# schem.net
KiCad netlist of a schematic drawn in Altium Designer
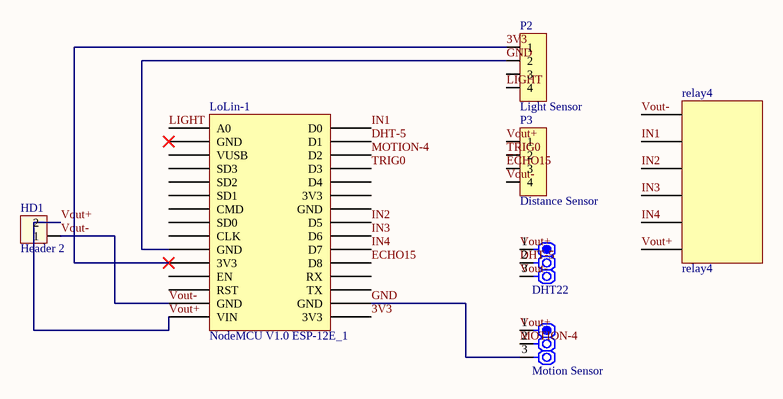
[diagram p0: schem.SchDoc]

(export (version "E")
  (design (tool "Eeschema 10.0.6"))
  (components
    (comp (ref "DHT22")
      (value "IO")
      (footprint "CON.HDR1X3")
      (description "Header 1x3")
      (fields (field (name "PUBLISHER") "Hoang Nguyen"))
      (libsource (lib "phong") (part "CON.HDR1x3"))
    )
    (comp (ref "HD1")
      (value "Header 2")
      (footprint "HED2")
      (description "Header 2 (Green)")
      (libsource (lib "syhaunguyen") (part "Hed2"))
    )
    (comp (ref "LoLin-1")
      (value "NodeMCU V1.0 ESP-12E_1")
      (footprint "LoLin NodeMcu V3")
      (description "LoLin NodeMCU V3")
      (libsource (lib "nodemcu") (part "NodeMCU V1.0 ESP-12E_1"))
    )
    (comp (ref "Motion Sensor")
      (value "IO")
      (footprint "CON.HDR1X3")
      (description "Header 1x3")
      (fields (field (name "PUBLISHER") "Hoang Nguyen"))
      (libsource (lib "phong") (part "CON.HDR1x3"))
    )
    (comp (ref "P2")
      (value "Light Sensor")
      (footprint "CON Header 4")
      (description "Header, 4-Pin")
      (libsource (lib "BKIT4U_LIB") (part "Header 4"))
    )
    (comp (ref "P3")
      (value "Distance Sensor")
      (footprint "CON Header 4")
      (description "Header, 4-Pin")
      (libsource (lib "BKIT4U_LIB") (part "Header 4"))
    )
    (comp (ref "relay4")
      (value "relay4")
      (footprint "PCBComponent_1")
      (libsource (lib "relay4") (part "relay4"))
    )
  )
  (nets
    (net (code "1") (name "/3V3") (class "Default")
      (node (ref "LoLin-1") (pin "3V3") (pinfunction "3V3_3V3") (pintype "passive"))
      (node (ref "P2") (pin "1") (pinfunction "1_1") (pintype "passive"))
    )
    (net (code "2") (name "/DHT-5") (class "Default")
      (node (ref "DHT22") (pin "2") (pinfunction "2_2") (pintype "passive"))
      (node (ref "LoLin-1") (pin "D1") (pinfunction "D1_D1") (pintype "passive"))
    )
    (net (code "3") (name "/ECHO15") (class "Default")
      (node (ref "LoLin-1") (pin "D8") (pinfunction "D8_D8") (pintype "passive"))
      (node (ref "P3") (pin "3") (pinfunction "3_3") (pintype "passive"))
    )
    (net (code "4") (name "/GND") (class "Default")
      (node (ref "LoLin-1") (pin "GND") (pinfunction "GND_GND") (pintype "passive"))
      (node (ref "Motion Sensor") (pin "3") (pinfunction "3_3") (pintype "passive"))
      (node (ref "P2") (pin "2") (pinfunction "2_2") (pintype "passive"))
    )
    (net (code "5") (name "/IN1") (class "Default")
      (node (ref "LoLin-1") (pin "D0") (pinfunction "D0_D0") (pintype "passive"))
      (node (ref "relay4") (pin "IN1") (pinfunction "IN1_IN1") (pintype "passive"))
    )
    (net (code "6") (name "/IN2") (class "Default")
      (node (ref "LoLin-1") (pin "D5") (pinfunction "D5_D5") (pintype "passive"))
      (node (ref "relay4") (pin "IN2") (pinfunction "IN2_IN2") (pintype "passive"))
    )
    (net (code "7") (name "/IN3") (class "Default")
      (node (ref "LoLin-1") (pin "D6") (pinfunction "D6_D6") (pintype "passive"))
      (node (ref "relay4") (pin "IN3") (pinfunction "IN3_IN3") (pintype "passive"))
    )
    (net (code "8") (name "/IN4") (class "Default")
      (node (ref "LoLin-1") (pin "D7") (pinfunction "D7_D7") (pintype "passive"))
      (node (ref "relay4") (pin "IN4") (pinfunction "IN4_IN4") (pintype "passive"))
    )
    (net (code "9") (name "/LIGHT") (class "Default")
      (node (ref "LoLin-1") (pin "A0") (pinfunction "A0_A0") (pintype "passive"))
      (node (ref "P2") (pin "4") (pinfunction "4_4") (pintype "passive"))
    )
    (net (code "10") (name "/MOTION-4") (class "Default")
      (node (ref "LoLin-1") (pin "D2") (pinfunction "D2_D2") (pintype "passive"))
      (node (ref "Motion Sensor") (pin "2") (pinfunction "2_2") (pintype "passive"))
    )
    (net (code "11") (name "/TRIG0") (class "Default")
      (node (ref "LoLin-1") (pin "D3") (pinfunction "D3_D3") (pintype "passive"))
      (node (ref "P3") (pin "2") (pinfunction "2_2") (pintype "passive"))
    )
    (net (code "12") (name "/Vout+") (class "Default")
      (node (ref "DHT22") (pin "1") (pinfunction "1_1") (pintype "passive"))
      (node (ref "HD1") (pin "2") (pinfunction "2_2") (pintype "passive"))
      (node (ref "LoLin-1") (pin "VIN") (pinfunction "VIN_VIN") (pintype "passive"))
      (node (ref "Motion Sensor") (pin "1") (pinfunction "1_1") (pintype "passive"))
      (node (ref "P3") (pin "1") (pinfunction "1_1") (pintype "passive"))
      (node (ref "relay4") (pin "VCC") (pinfunction "VCC_VCC") (pintype "passive"))
    )
    (net (code "13") (name "/Vout-") (class "Default")
      (node (ref "DHT22") (pin "3") (pinfunction "3_3") (pintype "passive"))
      (node (ref "HD1") (pin "1") (pinfunction "1_1") (pintype "passive"))
      (node (ref "LoLin-1") (pin "GND") (pinfunction "GND_GND") (pintype "passive"))
      (node (ref "P3") (pin "4") (pinfunction "4_4") (pintype "passive"))
      (node (ref "relay4") (pin "GND") (pinfunction "GND_GND") (pintype "passive"))
    )
    (net (code "14") (name "unconnected-(LoLin-1-Pad3V3)") (class "Default")
      (node (ref "LoLin-1") (pin "3V3") (pinfunction "3V3_3V3") (pintype "passive"))
    )
    (net (code "15") (name "unconnected-(LoLin-1-PadCLK)") (class "Default")
      (node (ref "LoLin-1") (pin "CLK") (pinfunction "CLK_CLK") (pintype "passive"))
    )
    (net (code "16") (name "unconnected-(LoLin-1-PadCMD)") (class "Default")
      (node (ref "LoLin-1") (pin "CMD") (pinfunction "CMD_CMD") (pintype "passive"))
    )
    (net (code "17") (name "unconnected-(LoLin-1-PadD4)") (class "Default")
      (node (ref "LoLin-1") (pin "D4") (pinfunction "D4_D4") (pintype "passive"))
    )
    (net (code "18") (name "unconnected-(LoLin-1-PadEN)") (class "Default")
      (node (ref "LoLin-1") (pin "EN") (pinfunction "EN_EN") (pintype "passive"))
    )
    (net (code "19") (name "unconnected-(LoLin-1-PadGND)") (class "Default")
      (node (ref "LoLin-1") (pin "GND") (pinfunction "GND_GND") (pintype "passive"))
    )
    (net (code "20") (name "unconnected-(LoLin-1-PadGND)") (class "Default")
      (node (ref "LoLin-1") (pin "GND") (pinfunction "GND_GND") (pintype "passive+no_connect"))
    )
    (net (code "21") (name "unconnected-(LoLin-1-PadRST)") (class "Default")
      (node (ref "LoLin-1") (pin "RST") (pinfunction "RST_RST") (pintype "passive"))
    )
    (net (code "22") (name "unconnected-(LoLin-1-PadRX)") (class "Default")
      (node (ref "LoLin-1") (pin "RX") (pinfunction "RX_RX") (pintype "passive"))
    )
    (net (code "23") (name "unconnected-(LoLin-1-PadSD0)") (class "Default")
      (node (ref "LoLin-1") (pin "SD0") (pinfunction "SD0_SD0") (pintype "passive"))
    )
    (net (code "24") (name "unconnected-(LoLin-1-PadSD1)") (class "Default")
      (node (ref "LoLin-1") (pin "SD1") (pinfunction "SD1_SD1") (pintype "passive"))
    )
    (net (code "25") (name "unconnected-(LoLin-1-PadSD2)") (class "Default")
      (node (ref "LoLin-1") (pin "SD2") (pinfunction "SD2_SD2") (pintype "passive"))
    )
    (net (code "26") (name "unconnected-(LoLin-1-PadSD3)") (class "Default")
      (node (ref "LoLin-1") (pin "SD3") (pinfunction "SD3_SD3") (pintype "passive"))
    )
    (net (code "27") (name "unconnected-(LoLin-1-PadTX)") (class "Default")
      (node (ref "LoLin-1") (pin "TX") (pinfunction "TX_TX") (pintype "passive"))
    )
    (net (code "28") (name "unconnected-(LoLin-1-PadVUSB)") (class "Default")
      (node (ref "LoLin-1") (pin "VUSB") (pinfunction "VUSB_VUSB") (pintype "passive"))
    )
    (net (code "29") (name "unconnected-(P2-Pad3)") (class "Default")
      (node (ref "P2") (pin "3") (pinfunction "3_3") (pintype "passive"))
    )
  )
)
